# Wi_Fi.net
KiCad netlist of a schematic drawn in Altium Designer
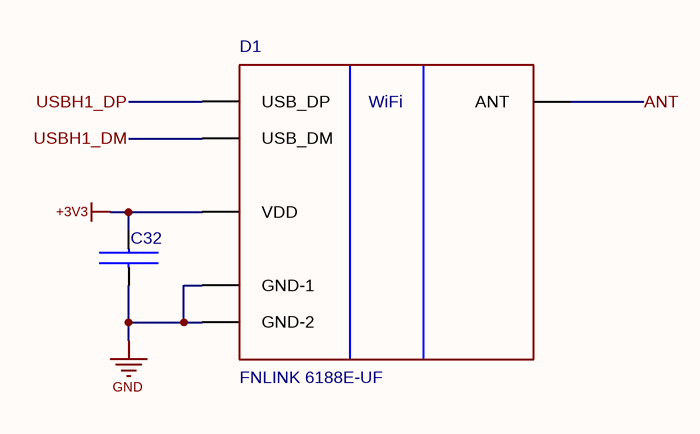
[diagram p0: Wi_Fi.SchDoc]

(export (version "E")
  (design (tool "Eeschema 10.0.6"))
  (components
    (comp (ref "C32")
      (value "0603-1uF-16V-10%-X7R")
      (fields (field (name "TOLERANCE") "10%"))
      (libsource (lib "altium-import") (part "root_1__*"))
    )
    (comp (ref "D1") (value "FNLINK 6188E-UF") (libsource (lib "altium-import") (part "root_0__*")))
  )
  (nets
    (net (code "1") (name "+3V3") (class "Default")
      (node (ref "C32") (pin "2") (pinfunction "2_2") (pintype "passive"))
      (node (ref "D1") (pin "3") (pinfunction "VDD_3") (pintype "passive"))
    )
    (net (code "2") (name "/ANT") (class "Default")
      (node (ref "D1") (pin "2") (pinfunction "ANT_2") (pintype "passive"))
    )
    (net (code "3") (name "/USBH1_DM") (class "Default")
      (node (ref "D1") (pin "4") (pinfunction "USB_DM_4") (pintype "passive"))
    )
    (net (code "4") (name "/USBH1_DP") (class "Default")
      (node (ref "D1") (pin "5") (pinfunction "USB_DP_5") (pintype "passive"))
    )
    (net (code "5") (name "GND") (class "Default")
      (node (ref "C32") (pin "1") (pinfunction "1_1") (pintype "passive"))
      (node (ref "D1") (pin "1") (pinfunction "GND-2_1") (pintype "power_in"))
      (node (ref "D1") (pin "6") (pinfunction "GND-1_6") (pintype "power_in"))
    )
  )
)
